# S123B.net
KiCad netlist of a schematic drawn in EAGLE
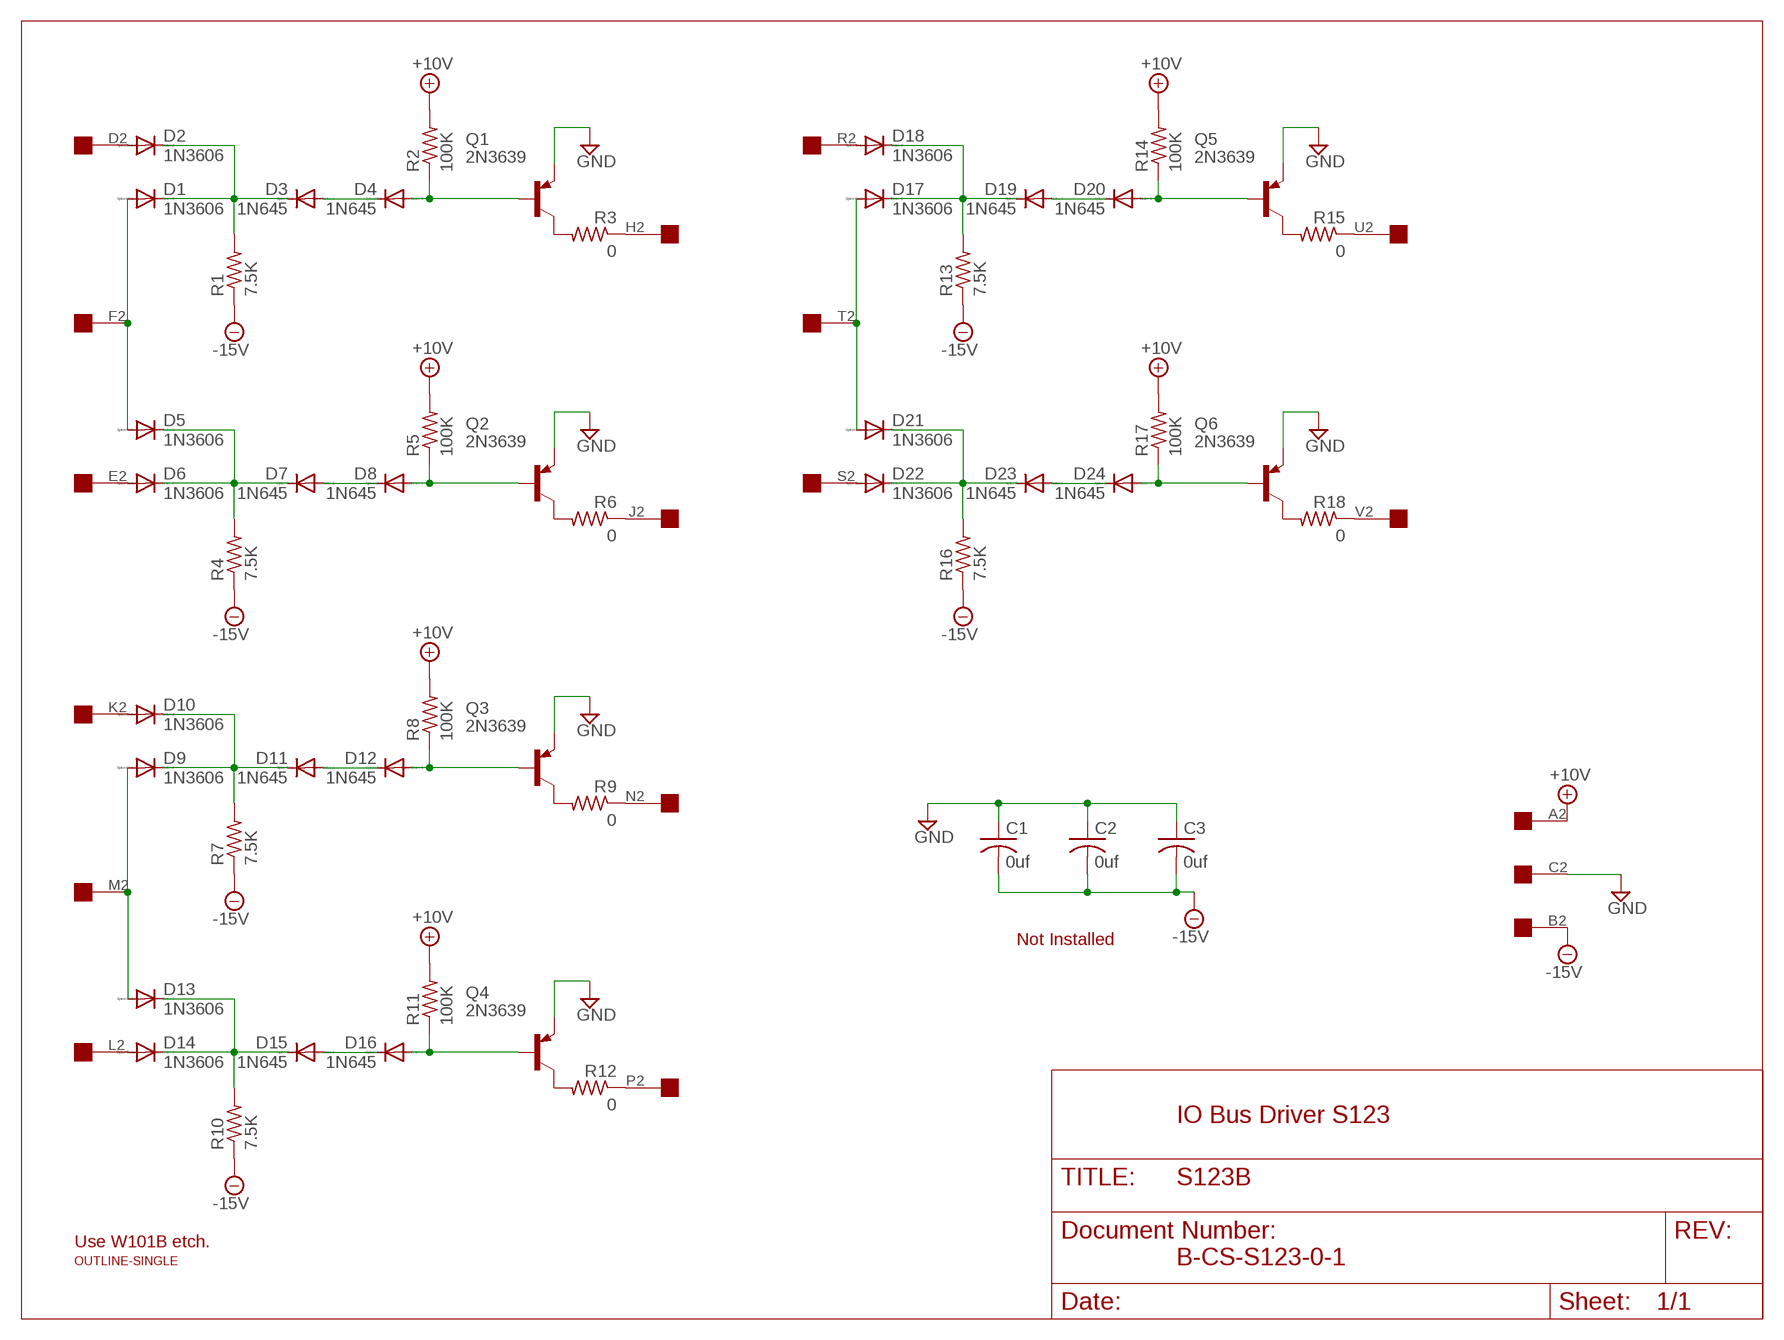
[diagram p0: schematic, sheet 1]

(export (version "E")
  (design (tool "Eeschema 10.0.6"))
  (components
    (comp (ref "C1")
      (value "0uf")
      (footprint "eagle-import:C050-025X075")
      (libsource (lib "eagle-import") (part "C-US050-025X075"))
    )
    (comp (ref "C2")
      (value "0uf")
      (footprint "eagle-import:C050-025X075")
      (libsource (lib "eagle-import") (part "C-US050-025X075"))
    )
    (comp (ref "C3")
      (value "0uf")
      (footprint "eagle-import:C050-025X075")
      (libsource (lib "eagle-import") (part "C-US050-025X075"))
    )
    (comp (ref "D1")
      (value "1N3606")
      (footprint "eagle-import:DO35-10")
      (libsource (lib "eagle-import") (part "1N4148DO35-10"))
    )
    (comp (ref "D2")
      (value "1N3606")
      (footprint "eagle-import:DO35-10")
      (libsource (lib "eagle-import") (part "1N4148DO35-10"))
    )
    (comp (ref "D3")
      (value "1N645")
      (footprint "eagle-import:DO35-10")
      (libsource (lib "eagle-import") (part "1N4148DO35-10"))
    )
    (comp (ref "D4")
      (value "1N645")
      (footprint "eagle-import:DO35-10")
      (libsource (lib "eagle-import") (part "1N4148DO35-10"))
    )
    (comp (ref "D5")
      (value "1N3606")
      (footprint "eagle-import:DO35-10")
      (libsource (lib "eagle-import") (part "1N4148DO35-10"))
    )
    (comp (ref "D6")
      (value "1N3606")
      (footprint "eagle-import:DO35-10")
      (libsource (lib "eagle-import") (part "1N4148DO35-10"))
    )
    (comp (ref "D7")
      (value "1N645")
      (footprint "eagle-import:DO35-10")
      (libsource (lib "eagle-import") (part "1N4148DO35-10"))
    )
    (comp (ref "D8")
      (value "1N645")
      (footprint "eagle-import:DO35-10")
      (libsource (lib "eagle-import") (part "1N4148DO35-10"))
    )
    (comp (ref "D9")
      (value "1N3606")
      (footprint "eagle-import:DO35-10")
      (libsource (lib "eagle-import") (part "1N4148DO35-10"))
    )
    (comp (ref "D10")
      (value "1N3606")
      (footprint "eagle-import:DO35-10")
      (libsource (lib "eagle-import") (part "1N4148DO35-10"))
    )
    (comp (ref "D11")
      (value "1N645")
      (footprint "eagle-import:DO35-10")
      (libsource (lib "eagle-import") (part "1N4148DO35-10"))
    )
    (comp (ref "D12")
      (value "1N645")
      (footprint "eagle-import:DO35-10")
      (libsource (lib "eagle-import") (part "1N4148DO35-10"))
    )
    (comp (ref "D13")
      (value "1N3606")
      (footprint "eagle-import:DO35-10")
      (libsource (lib "eagle-import") (part "1N4148DO35-10"))
    )
    (comp (ref "D14")
      (value "1N3606")
      (footprint "eagle-import:DO35-10")
      (libsource (lib "eagle-import") (part "1N4148DO35-10"))
    )
    (comp (ref "D15")
      (value "1N645")
      (footprint "eagle-import:DO35-10")
      (libsource (lib "eagle-import") (part "1N4148DO35-10"))
    )
    (comp (ref "D16")
      (value "1N645")
      (footprint "eagle-import:DO35-10")
      (libsource (lib "eagle-import") (part "1N4148DO35-10"))
    )
    (comp (ref "D17")
      (value "1N3606")
      (footprint "eagle-import:DO35-10")
      (libsource (lib "eagle-import") (part "1N4148DO35-10"))
    )
    (comp (ref "D18")
      (value "1N3606")
      (footprint "eagle-import:DO35-10")
      (libsource (lib "eagle-import") (part "1N4148DO35-10"))
    )
    (comp (ref "D19")
      (value "1N645")
      (footprint "eagle-import:DO35-10")
      (libsource (lib "eagle-import") (part "1N4148DO35-10"))
    )
    (comp (ref "D20")
      (value "1N645")
      (footprint "eagle-import:DO35-10")
      (libsource (lib "eagle-import") (part "1N4148DO35-10"))
    )
    (comp (ref "D21")
      (value "1N3606")
      (footprint "eagle-import:DO35-10")
      (libsource (lib "eagle-import") (part "1N4148DO35-10"))
    )
    (comp (ref "D22")
      (value "1N3606")
      (footprint "eagle-import:DO35-10")
      (libsource (lib "eagle-import") (part "1N4148DO35-10"))
    )
    (comp (ref "D23")
      (value "1N645")
      (footprint "eagle-import:DO35-10")
      (libsource (lib "eagle-import") (part "1N4148DO35-10"))
    )
    (comp (ref "D24")
      (value "1N645")
      (footprint "eagle-import:DO35-10")
      (libsource (lib "eagle-import") (part "1N4148DO35-10"))
    )
    (comp (ref "Q1")
      (value "2N3639")
      (footprint "eagle-import:TO39")
      (libsource (lib "eagle-import") (part "2N3637"))
    )
    (comp (ref "Q2")
      (value "2N3639")
      (footprint "eagle-import:TO39")
      (libsource (lib "eagle-import") (part "2N3637"))
    )
    (comp (ref "Q3")
      (value "2N3639")
      (footprint "eagle-import:TO39")
      (libsource (lib "eagle-import") (part "2N3637"))
    )
    (comp (ref "Q4")
      (value "2N3639")
      (footprint "eagle-import:TO39")
      (libsource (lib "eagle-import") (part "2N3637"))
    )
    (comp (ref "Q5")
      (value "2N3639")
      (footprint "eagle-import:TO39")
      (libsource (lib "eagle-import") (part "2N3637"))
    )
    (comp (ref "Q6")
      (value "2N3639")
      (footprint "eagle-import:TO39")
      (libsource (lib "eagle-import") (part "2N3637"))
    )
    (comp (ref "R1")
      (value "7.5K")
      (footprint "eagle-import:0207_10")
      (libsource (lib "eagle-import") (part "R-US_0207/10"))
    )
    (comp (ref "R2")
      (value "100K")
      (footprint "eagle-import:0207_10")
      (libsource (lib "eagle-import") (part "R-US_0207/10"))
    )
    (comp (ref "R3")
      (value "0")
      (footprint "eagle-import:0207_10")
      (libsource (lib "eagle-import") (part "R-US_0207/10"))
    )
    (comp (ref "R4")
      (value "7.5K")
      (footprint "eagle-import:0207_10")
      (libsource (lib "eagle-import") (part "R-US_0207/10"))
    )
    (comp (ref "R5")
      (value "100K")
      (footprint "eagle-import:0207_10")
      (libsource (lib "eagle-import") (part "R-US_0207/10"))
    )
    (comp (ref "R6")
      (value "0")
      (footprint "eagle-import:0207_10")
      (libsource (lib "eagle-import") (part "R-US_0207/10"))
    )
    (comp (ref "R7")
      (value "7.5K")
      (footprint "eagle-import:0207_10")
      (libsource (lib "eagle-import") (part "R-US_0207/10"))
    )
    (comp (ref "R8")
      (value "100K")
      (footprint "eagle-import:0207_10")
      (libsource (lib "eagle-import") (part "R-US_0207/10"))
    )
    (comp (ref "R9")
      (value "0")
      (footprint "eagle-import:0207_10")
      (libsource (lib "eagle-import") (part "R-US_0207/10"))
    )
    (comp (ref "R10")
      (value "7.5K")
      (footprint "eagle-import:0207_10")
      (libsource (lib "eagle-import") (part "R-US_0207/10"))
    )
    (comp (ref "R11")
      (value "100K")
      (footprint "eagle-import:0207_10")
      (libsource (lib "eagle-import") (part "R-US_0207/10"))
    )
    (comp (ref "R12")
      (value "0")
      (footprint "eagle-import:0207_10")
      (libsource (lib "eagle-import") (part "R-US_0207/10"))
    )
    (comp (ref "R13")
      (value "7.5K")
      (footprint "eagle-import:0207_10")
      (libsource (lib "eagle-import") (part "R-US_0207/10"))
    )
    (comp (ref "R14")
      (value "100K")
      (footprint "eagle-import:0207_10")
      (libsource (lib "eagle-import") (part "R-US_0207/10"))
    )
    (comp (ref "R15")
      (value "0")
      (footprint "eagle-import:0207_10")
      (libsource (lib "eagle-import") (part "R-US_0207/10"))
    )
    (comp (ref "R16")
      (value "7.5K")
      (footprint "eagle-import:0207_10")
      (libsource (lib "eagle-import") (part "R-US_0207/10"))
    )
    (comp (ref "R17")
      (value "100K")
      (footprint "eagle-import:0207_10")
      (libsource (lib "eagle-import") (part "R-US_0207/10"))
    )
    (comp (ref "R18")
      (value "0")
      (footprint "eagle-import:0207_10")
      (libsource (lib "eagle-import") (part "R-US_0207/10"))
    )
    (comp (ref "U$1")
      (value "OUTLINE-SINGLE")
      (footprint "eagle-import:SINGLE")
      (libsource (lib "eagle-import") (part "OUTLINE-SINGLE"))
    )
    (comp (ref "U$2")
      (value "EDGE-1")
      (footprint "eagle-import:EDGE-CON1")
      (libsource (lib "eagle-import") (part "EDGE-1"))
    )
  )
  (nets
    (net (code "1") (name "+10V") (class "Default")
      (node (ref "R11") (pin "2") (pinfunction "2_2") (pintype "passive"))
      (node (ref "R14") (pin "2") (pinfunction "2_2") (pintype "passive"))
      (node (ref "R17") (pin "2") (pinfunction "2_2") (pintype "passive"))
      (node (ref "R2") (pin "2") (pinfunction "2_2") (pintype "passive"))
      (node (ref "R5") (pin "2") (pinfunction "2_2") (pintype "passive"))
      (node (ref "R8") (pin "2") (pinfunction "2_2") (pintype "passive"))
      (node (ref "U$2") (pin "A2") (pinfunction "1_A2") (pintype "bidirectional"))
    )
    (net (code "2") (name "-15V") (class "Default")
      (node (ref "C1") (pin "2") (pinfunction "2_2") (pintype "passive"))
      (node (ref "C2") (pin "2") (pinfunction "2_2") (pintype "passive"))
      (node (ref "C3") (pin "2") (pinfunction "2_2") (pintype "passive"))
      (node (ref "R1") (pin "1") (pinfunction "1_1") (pintype "passive"))
      (node (ref "R10") (pin "1") (pinfunction "1_1") (pintype "passive"))
      (node (ref "R13") (pin "1") (pinfunction "1_1") (pintype "passive"))
      (node (ref "R16") (pin "1") (pinfunction "1_1") (pintype "passive"))
      (node (ref "R4") (pin "1") (pinfunction "1_1") (pintype "passive"))
      (node (ref "R7") (pin "1") (pinfunction "1_1") (pintype "passive"))
      (node (ref "U$2") (pin "B2") (pinfunction "1_B2") (pintype "bidirectional"))
    )
    (net (code "3") (name "GND") (class "Default")
      (node (ref "C1") (pin "1") (pinfunction "1_1") (pintype "passive"))
      (node (ref "C2") (pin "1") (pinfunction "1_1") (pintype "passive"))
      (node (ref "C3") (pin "1") (pinfunction "1_1") (pintype "passive"))
      (node (ref "Q1") (pin "1") (pinfunction "E_1") (pintype "passive"))
      (node (ref "Q2") (pin "1") (pinfunction "E_1") (pintype "passive"))
      (node (ref "Q3") (pin "1") (pinfunction "E_1") (pintype "passive"))
      (node (ref "Q4") (pin "1") (pinfunction "E_1") (pintype "passive"))
      (node (ref "Q5") (pin "1") (pinfunction "E_1") (pintype "passive"))
      (node (ref "Q6") (pin "1") (pinfunction "E_1") (pintype "passive"))
      (node (ref "U$2") (pin "C2") (pinfunction "1_C2") (pintype "bidirectional"))
    )
    (net (code "4") (name "Net-(D1-PadC)") (class "Default")
      (node (ref "D1") (pin "C") (pinfunction "C_C") (pintype "passive"))
      (node (ref "D2") (pin "C") (pinfunction "C_C") (pintype "passive"))
      (node (ref "D3") (pin "C") (pinfunction "C_C") (pintype "passive"))
      (node (ref "R1") (pin "2") (pinfunction "2_2") (pintype "passive"))
    )
    (net (code "5") (name "Net-(D3-PadA)") (class "Default")
      (node (ref "D3") (pin "A") (pinfunction "A_A") (pintype "passive"))
      (node (ref "D4") (pin "C") (pinfunction "C_C") (pintype "passive"))
    )
    (net (code "6") (name "Net-(D5-PadC)") (class "Default")
      (node (ref "D5") (pin "C") (pinfunction "C_C") (pintype "passive"))
      (node (ref "D6") (pin "C") (pinfunction "C_C") (pintype "passive"))
      (node (ref "D7") (pin "C") (pinfunction "C_C") (pintype "passive"))
      (node (ref "R4") (pin "2") (pinfunction "2_2") (pintype "passive"))
    )
    (net (code "7") (name "Net-(D7-PadA)") (class "Default")
      (node (ref "D7") (pin "A") (pinfunction "A_A") (pintype "passive"))
      (node (ref "D8") (pin "C") (pinfunction "C_C") (pintype "passive"))
    )
    (net (code "8") (name "Net-(D10-PadC)") (class "Default")
      (node (ref "D10") (pin "C") (pinfunction "C_C") (pintype "passive"))
      (node (ref "D11") (pin "C") (pinfunction "C_C") (pintype "passive"))
      (node (ref "D9") (pin "C") (pinfunction "C_C") (pintype "passive"))
      (node (ref "R7") (pin "2") (pinfunction "2_2") (pintype "passive"))
    )
    (net (code "9") (name "Net-(D11-PadA)") (class "Default")
      (node (ref "D11") (pin "A") (pinfunction "A_A") (pintype "passive"))
      (node (ref "D12") (pin "C") (pinfunction "C_C") (pintype "passive"))
    )
    (net (code "10") (name "Net-(D13-PadC)") (class "Default")
      (node (ref "D13") (pin "C") (pinfunction "C_C") (pintype "passive"))
      (node (ref "D14") (pin "C") (pinfunction "C_C") (pintype "passive"))
      (node (ref "D15") (pin "C") (pinfunction "C_C") (pintype "passive"))
      (node (ref "R10") (pin "2") (pinfunction "2_2") (pintype "passive"))
    )
    (net (code "11") (name "Net-(D15-PadA)") (class "Default")
      (node (ref "D15") (pin "A") (pinfunction "A_A") (pintype "passive"))
      (node (ref "D16") (pin "C") (pinfunction "C_C") (pintype "passive"))
    )
    (net (code "12") (name "Net-(D17-PadC)") (class "Default")
      (node (ref "D17") (pin "C") (pinfunction "C_C") (pintype "passive"))
      (node (ref "D18") (pin "C") (pinfunction "C_C") (pintype "passive"))
      (node (ref "D19") (pin "C") (pinfunction "C_C") (pintype "passive"))
      (node (ref "R13") (pin "2") (pinfunction "2_2") (pintype "passive"))
    )
    (net (code "13") (name "Net-(D19-PadA)") (class "Default")
      (node (ref "D19") (pin "A") (pinfunction "A_A") (pintype "passive"))
      (node (ref "D20") (pin "C") (pinfunction "C_C") (pintype "passive"))
    )
    (net (code "14") (name "Net-(D21-PadC)") (class "Default")
      (node (ref "D21") (pin "C") (pinfunction "C_C") (pintype "passive"))
      (node (ref "D22") (pin "C") (pinfunction "C_C") (pintype "passive"))
      (node (ref "D23") (pin "C") (pinfunction "C_C") (pintype "passive"))
      (node (ref "R16") (pin "2") (pinfunction "2_2") (pintype "passive"))
    )
    (net (code "15") (name "Net-(D23-PadA)") (class "Default")
      (node (ref "D23") (pin "A") (pinfunction "A_A") (pintype "passive"))
      (node (ref "D24") (pin "C") (pinfunction "C_C") (pintype "passive"))
    )
    (net (code "16") (name "Net-(Q1-B)") (class "Default")
      (node (ref "D4") (pin "A") (pinfunction "A_A") (pintype "passive"))
      (node (ref "Q1") (pin "2") (pinfunction "B_2") (pintype "passive"))
      (node (ref "R2") (pin "1") (pinfunction "1_1") (pintype "passive"))
    )
    (net (code "17") (name "Net-(Q1-C)") (class "Default")
      (node (ref "Q1") (pin "3") (pinfunction "C_3") (pintype "passive"))
      (node (ref "R3") (pin "2") (pinfunction "2_2") (pintype "passive"))
    )
    (net (code "18") (name "Net-(Q2-B)") (class "Default")
      (node (ref "D8") (pin "A") (pinfunction "A_A") (pintype "passive"))
      (node (ref "Q2") (pin "2") (pinfunction "B_2") (pintype "passive"))
      (node (ref "R5") (pin "1") (pinfunction "1_1") (pintype "passive"))
    )
    (net (code "19") (name "Net-(Q2-C)") (class "Default")
      (node (ref "Q2") (pin "3") (pinfunction "C_3") (pintype "passive"))
      (node (ref "R6") (pin "2") (pinfunction "2_2") (pintype "passive"))
    )
    (net (code "20") (name "Net-(Q3-B)") (class "Default")
      (node (ref "D12") (pin "A") (pinfunction "A_A") (pintype "passive"))
      (node (ref "Q3") (pin "2") (pinfunction "B_2") (pintype "passive"))
      (node (ref "R8") (pin "1") (pinfunction "1_1") (pintype "passive"))
    )
    (net (code "21") (name "Net-(Q3-C)") (class "Default")
      (node (ref "Q3") (pin "3") (pinfunction "C_3") (pintype "passive"))
      (node (ref "R9") (pin "2") (pinfunction "2_2") (pintype "passive"))
    )
    (net (code "22") (name "Net-(Q4-B)") (class "Default")
      (node (ref "D16") (pin "A") (pinfunction "A_A") (pintype "passive"))
      (node (ref "Q4") (pin "2") (pinfunction "B_2") (pintype "passive"))
      (node (ref "R11") (pin "1") (pinfunction "1_1") (pintype "passive"))
    )
    (net (code "23") (name "Net-(Q4-C)") (class "Default")
      (node (ref "Q4") (pin "3") (pinfunction "C_3") (pintype "passive"))
      (node (ref "R12") (pin "2") (pinfunction "2_2") (pintype "passive"))
    )
    (net (code "24") (name "Net-(Q5-B)") (class "Default")
      (node (ref "D20") (pin "A") (pinfunction "A_A") (pintype "passive"))
      (node (ref "Q5") (pin "2") (pinfunction "B_2") (pintype "passive"))
      (node (ref "R14") (pin "1") (pinfunction "1_1") (pintype "passive"))
    )
    (net (code "25") (name "Net-(Q5-C)") (class "Default")
      (node (ref "Q5") (pin "3") (pinfunction "C_3") (pintype "passive"))
      (node (ref "R15") (pin "2") (pinfunction "2_2") (pintype "passive"))
    )
    (net (code "26") (name "Net-(Q6-B)") (class "Default")
      (node (ref "D24") (pin "A") (pinfunction "A_A") (pintype "passive"))
      (node (ref "Q6") (pin "2") (pinfunction "B_2") (pintype "passive"))
      (node (ref "R17") (pin "1") (pinfunction "1_1") (pintype "passive"))
    )
    (net (code "27") (name "Net-(Q6-C)") (class "Default")
      (node (ref "Q6") (pin "3") (pinfunction "C_3") (pintype "passive"))
      (node (ref "R18") (pin "2") (pinfunction "2_2") (pintype "passive"))
    )
    (net (code "28") (name "Net-(U$2D-1)") (class "Default")
      (node (ref "D2") (pin "A") (pinfunction "A_A") (pintype "passive"))
      (node (ref "U$2") (pin "D2") (pinfunction "1_D2") (pintype "bidirectional"))
    )
    (net (code "29") (name "Net-(U$2E-1)") (class "Default")
      (node (ref "D6") (pin "A") (pinfunction "A_A") (pintype "passive"))
      (node (ref "U$2") (pin "E2") (pinfunction "1_E2") (pintype "bidirectional"))
    )
    (net (code "30") (name "Net-(U$2F-1)") (class "Default")
      (node (ref "D1") (pin "A") (pinfunction "A_A") (pintype "passive"))
      (node (ref "D5") (pin "A") (pinfunction "A_A") (pintype "passive"))
      (node (ref "U$2") (pin "F2") (pinfunction "1_F2") (pintype "bidirectional"))
    )
    (net (code "31") (name "Net-(U$2G-1)") (class "Default")
      (node (ref "R3") (pin "1") (pinfunction "1_1") (pintype "passive"))
      (node (ref "U$2") (pin "H2") (pinfunction "1_H2") (pintype "bidirectional"))
    )
    (net (code "32") (name "Net-(U$2H-1)") (class "Default")
      (node (ref "R6") (pin "1") (pinfunction "1_1") (pintype "passive"))
      (node (ref "U$2") (pin "J2") (pinfunction "1_J2") (pintype "bidirectional"))
    )
    (net (code "33") (name "Net-(U$2I-1)") (class "Default")
      (node (ref "D10") (pin "A") (pinfunction "A_A") (pintype "passive"))
      (node (ref "U$2") (pin "K2") (pinfunction "1_K2") (pintype "bidirectional"))
    )
    (net (code "34") (name "Net-(U$2J-1)") (class "Default")
      (node (ref "D14") (pin "A") (pinfunction "A_A") (pintype "passive"))
      (node (ref "U$2") (pin "L2") (pinfunction "1_L2") (pintype "bidirectional"))
    )
    (net (code "35") (name "Net-(U$2K-1)") (class "Default")
      (node (ref "D13") (pin "A") (pinfunction "A_A") (pintype "passive"))
      (node (ref "D9") (pin "A") (pinfunction "A_A") (pintype "passive"))
      (node (ref "U$2") (pin "M2") (pinfunction "1_M2") (pintype "bidirectional"))
    )
    (net (code "36") (name "Net-(U$2L-1)") (class "Default")
      (node (ref "R9") (pin "1") (pinfunction "1_1") (pintype "passive"))
      (node (ref "U$2") (pin "N2") (pinfunction "1_N2") (pintype "bidirectional"))
    )
    (net (code "37") (name "Net-(U$2M-1)") (class "Default")
      (node (ref "R12") (pin "1") (pinfunction "1_1") (pintype "passive"))
      (node (ref "U$2") (pin "P2") (pinfunction "1_P2") (pintype "bidirectional"))
    )
    (net (code "38") (name "Net-(U$2N-1)") (class "Default")
      (node (ref "D18") (pin "A") (pinfunction "A_A") (pintype "passive"))
      (node (ref "U$2") (pin "R2") (pinfunction "1_R2") (pintype "bidirectional"))
    )
    (net (code "39") (name "Net-(U$2O-1)") (class "Default")
      (node (ref "D22") (pin "A") (pinfunction "A_A") (pintype "passive"))
      (node (ref "U$2") (pin "S2") (pinfunction "1_S2") (pintype "bidirectional"))
    )
    (net (code "40") (name "Net-(U$2P-1)") (class "Default")
      (node (ref "D17") (pin "A") (pinfunction "A_A") (pintype "passive"))
      (node (ref "D21") (pin "A") (pinfunction "A_A") (pintype "passive"))
      (node (ref "U$2") (pin "T2") (pinfunction "1_T2") (pintype "bidirectional"))
    )
    (net (code "41") (name "Net-(U$2Q-1)") (class "Default")
      (node (ref "R15") (pin "1") (pinfunction "1_1") (pintype "passive"))
      (node (ref "U$2") (pin "U2") (pinfunction "1_U2") (pintype "bidirectional"))
    )
    (net (code "42") (name "Net-(U$2R-1)") (class "Default")
      (node (ref "R18") (pin "1") (pinfunction "1_1") (pintype "passive"))
      (node (ref "U$2") (pin "V2") (pinfunction "1_V2") (pintype "bidirectional"))
    )
  )
)
